# Main_Board.net
KiCad netlist of a schematic drawn in EAGLE
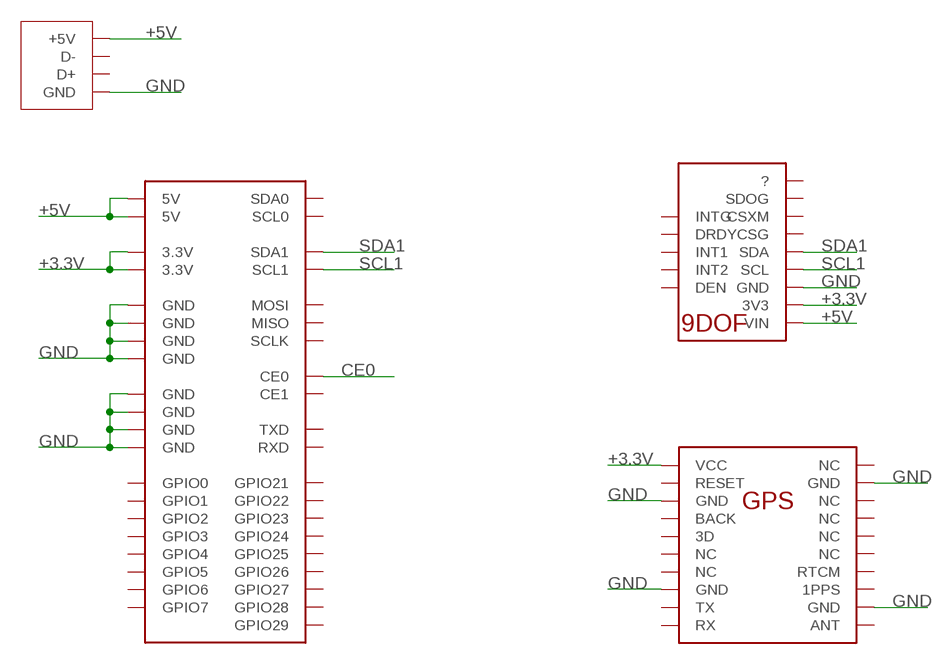
[diagram p0: schematic, sheet 1]

(export (version "E")
  (design (tool "Eeschema 10.0.6"))
  (components
    (comp (ref "U$5")
      (value "GPS")
      (footprint "eagle-import:GPS")
      (libsource (lib "eagle-import") (part "GPS"))
    )
    (comp (ref "U$6")
      (value "9DOF")
      (footprint "eagle-import:9DOF")
      (libsource (lib "eagle-import") (part "9DOF"))
    )
    (comp (ref "U$8")
      (value "USB_VERTICLE")
      (footprint "eagle-import:USB_VERTICLE")
      (libsource (lib "eagle-import") (part "USB_VERTICLE"))
    )
    (comp (ref "U$11")
      (value "PI")
      (footprint "eagle-import:PI_HEADER_SMD")
      (libsource (lib "eagle-import") (part "PI"))
    )
  )
  (nets
    (net (code "1") (name "+3.3V") (class "Default")
      (node (ref "U$11") (pin "3.3V@1") (pinfunction "3.3V_3.3V@1") (pintype "bidirectional"))
      (node (ref "U$11") (pin "3.3V@17") (pinfunction "3.3V_3.3V@17") (pintype "bidirectional"))
      (node (ref "U$5") (pin "P$1") (pinfunction "VCC_P$1") (pintype "bidirectional"))
      (node (ref "U$6") (pin "P$21") (pinfunction "3V3_P$21") (pintype "bidirectional"))
    )
    (net (code "2") (name "+5V") (class "Default")
      (node (ref "U$11") (pin "5V@2") (pinfunction "5V_5V@2") (pintype "bidirectional"))
      (node (ref "U$11") (pin "5V@4") (pinfunction "5V_5V@4") (pintype "bidirectional"))
      (node (ref "U$6") (pin "P$20") (pinfunction "VIN_P$20") (pintype "bidirectional"))
      (node (ref "U$8") (pin "VCC") (pinfunction "+5V_VCC") (pintype "bidirectional"))
    )
    (net (code "3") (name "CE0") (class "Default")
      (node (ref "U$11") (pin "CE0") (pinfunction "CE0_CE0") (pintype "bidirectional"))
    )
    (net (code "4") (name "GND") (class "Default")
      (node (ref "U$11") (pin "GND@14") (pinfunction "GND_GND@14") (pintype "bidirectional"))
      (node (ref "U$11") (pin "GND@20") (pinfunction "GND_GND@20") (pintype "bidirectional"))
      (node (ref "U$11") (pin "GND@25") (pinfunction "GND_GND@25") (pintype "bidirectional"))
      (node (ref "U$11") (pin "GND@30") (pinfunction "GND_GND@30") (pintype "bidirectional"))
      (node (ref "U$11") (pin "GND@34") (pinfunction "GND_GND@34") (pintype "bidirectional"))
      (node (ref "U$11") (pin "GND@39") (pinfunction "GND_GND@39") (pintype "bidirectional"))
      (node (ref "U$11") (pin "GND@6") (pinfunction "GND_GND@6") (pintype "bidirectional"))
      (node (ref "U$11") (pin "GND@9") (pinfunction "GND_GND@9") (pintype "bidirectional"))
      (node (ref "U$5") (pin "P$12") (pinfunction "GND_P$12") (pintype "bidirectional"))
      (node (ref "U$5") (pin "P$19") (pinfunction "GND_P$19") (pintype "bidirectional"))
      (node (ref "U$5") (pin "P$3") (pinfunction "GND_P$3") (pintype "bidirectional"))
      (node (ref "U$5") (pin "P$8") (pinfunction "GND_P$8") (pintype "bidirectional"))
      (node (ref "U$6") (pin "P$22") (pinfunction "GND_P$22") (pintype "bidirectional"))
      (node (ref "U$8") (pin "GND@1") (pinfunction "GND_GND@1") (pintype "bidirectional"))
      (node (ref "U$8") (pin "GND@2") (pinfunction "GND_GND@2") (pintype "bidirectional"))
      (node (ref "U$8") (pin "GND@3") (pinfunction "GND_GND@3") (pintype "bidirectional"))
    )
    (net (code "5") (name "SCL1") (class "Default")
      (node (ref "U$11") (pin "SCL1") (pinfunction "SCL1_SCL1") (pintype "bidirectional"))
      (node (ref "U$6") (pin "P$23") (pinfunction "SCL_P$23") (pintype "bidirectional"))
    )
    (net (code "6") (name "SDA1") (class "Default")
      (node (ref "U$11") (pin "SDA1") (pinfunction "SDA1_SDA1") (pintype "bidirectional"))
      (node (ref "U$6") (pin "P$24") (pinfunction "SDA_P$24") (pintype "bidirectional"))
    )
    (net (code "7") (name "unconnected-(U$5-1PPS-PadP$13)") (class "Default")
      (node (ref "U$5") (pin "P$13") (pinfunction "1PPS_P$13") (pintype "bidirectional"))
    )
    (net (code "8") (name "unconnected-(U$5-3D-PadP$5)") (class "Default")
      (node (ref "U$5") (pin "P$5") (pinfunction "3D_P$5") (pintype "bidirectional"))
    )
    (net (code "9") (name "unconnected-(U$5-ANT-PadP$11)") (class "Default")
      (node (ref "U$5") (pin "P$11") (pinfunction "ANT_P$11") (pintype "bidirectional"))
    )
    (net (code "10") (name "unconnected-(U$5-BACK-PadP$4)") (class "Default")
      (node (ref "U$5") (pin "P$4") (pinfunction "BACK_P$4") (pintype "bidirectional"))
    )
    (net (code "11") (name "unconnected-(U$5-NC-PadP$6)") (class "Default")
      (node (ref "U$5") (pin "P$6") (pinfunction "NC_P$6") (pintype "bidirectional"))
    )
    (net (code "12") (name "unconnected-(U$5-NC-PadP$7)") (class "Default")
      (node (ref "U$5") (pin "P$7") (pinfunction "NC_P$7") (pintype "bidirectional"))
    )
    (net (code "13") (name "unconnected-(U$5-NC-PadP$15)") (class "Default")
      (node (ref "U$5") (pin "P$15") (pinfunction "NC_P$15") (pintype "bidirectional"))
    )
    (net (code "14") (name "unconnected-(U$5-NC-PadP$16)") (class "Default")
      (node (ref "U$5") (pin "P$16") (pinfunction "NC_P$16") (pintype "bidirectional"))
    )
    (net (code "15") (name "unconnected-(U$5-NC-PadP$17)") (class "Default")
      (node (ref "U$5") (pin "P$17") (pinfunction "NC_P$17") (pintype "bidirectional"))
    )
    (net (code "16") (name "unconnected-(U$5-NC-PadP$18)") (class "Default")
      (node (ref "U$5") (pin "P$18") (pinfunction "NC_P$18") (pintype "bidirectional"))
    )
    (net (code "17") (name "unconnected-(U$5-NC-PadP$20)") (class "Default")
      (node (ref "U$5") (pin "P$20") (pinfunction "NC_P$20") (pintype "bidirectional"))
    )
    (net (code "18") (name "unconnected-(U$5-RESET-PadP$2)") (class "Default")
      (node (ref "U$5") (pin "P$2") (pinfunction "RESET_P$2") (pintype "bidirectional"))
    )
    (net (code "19") (name "unconnected-(U$5-RTCM-PadP$14)") (class "Default")
      (node (ref "U$5") (pin "P$14") (pinfunction "RTCM_P$14") (pintype "bidirectional"))
    )
    (net (code "20") (name "unconnected-(U$5-RX-PadP$10)") (class "Default")
      (node (ref "U$5") (pin "P$10") (pinfunction "RX_P$10") (pintype "bidirectional"))
    )
    (net (code "21") (name "unconnected-(U$5-TX-PadP$9)") (class "Default")
      (node (ref "U$5") (pin "P$9") (pinfunction "TX_P$9") (pintype "bidirectional"))
    )
    (net (code "22") (name "unconnected-(U$6-?-PadP$28)") (class "Default")
      (node (ref "U$6") (pin "P$28") (pinfunction "?_P$28") (pintype "bidirectional"))
    )
    (net (code "23") (name "unconnected-(U$6-CSG-PadP$25)") (class "Default")
      (node (ref "U$6") (pin "P$25") (pinfunction "CSG_P$25") (pintype "bidirectional"))
    )
    (net (code "24") (name "unconnected-(U$6-CSXM-PadP$26)") (class "Default")
      (node (ref "U$6") (pin "P$26") (pinfunction "CSXM_P$26") (pintype "bidirectional"))
    )
    (net (code "25") (name "unconnected-(U$6-DEN-PadP$15)") (class "Default")
      (node (ref "U$6") (pin "P$15") (pinfunction "DEN_P$15") (pintype "bidirectional"))
    )
    (net (code "26") (name "unconnected-(U$6-DRDY-PadP$18)") (class "Default")
      (node (ref "U$6") (pin "P$18") (pinfunction "DRDY_P$18") (pintype "bidirectional"))
    )
    (net (code "27") (name "unconnected-(U$6-INT1-PadP$17)") (class "Default")
      (node (ref "U$6") (pin "P$17") (pinfunction "INT1_P$17") (pintype "bidirectional"))
    )
    (net (code "28") (name "unconnected-(U$6-INT2-PadP$16)") (class "Default")
      (node (ref "U$6") (pin "P$16") (pinfunction "INT2_P$16") (pintype "bidirectional"))
    )
    (net (code "29") (name "unconnected-(U$6-INTG-PadP$19)") (class "Default")
      (node (ref "U$6") (pin "P$19") (pinfunction "INTG_P$19") (pintype "bidirectional"))
    )
    (net (code "30") (name "unconnected-(U$6-SDOG-PadP$27)") (class "Default")
      (node (ref "U$6") (pin "P$27") (pinfunction "SDOG_P$27") (pintype "bidirectional"))
    )
    (net (code "31") (name "unconnected-(U$8-PadD+)") (class "Default")
      (node (ref "U$8") (pin "D+") (pinfunction "D+_D+") (pintype "bidirectional"))
    )
    (net (code "32") (name "unconnected-(U$8-PadD-)") (class "Default")
      (node (ref "U$8") (pin "D-") (pinfunction "D-_D-") (pintype "bidirectional"))
    )
    (net (code "33") (name "unconnected-(U$11-PadCE1)") (class "Default")
      (node (ref "U$11") (pin "CE1") (pinfunction "CE1_CE1") (pintype "bidirectional"))
    )
    (net (code "34") (name "unconnected-(U$11-PadGPIO0)") (class "Default")
      (node (ref "U$11") (pin "GPIO0") (pinfunction "GPIO0_GPIO0") (pintype "bidirectional"))
    )
    (net (code "35") (name "unconnected-(U$11-PadGPIO1)") (class "Default")
      (node (ref "U$11") (pin "GPIO1") (pinfunction "GPIO1_GPIO1") (pintype "bidirectional"))
    )
    (net (code "36") (name "unconnected-(U$11-PadGPIO2)") (class "Default")
      (node (ref "U$11") (pin "GPIO2") (pinfunction "GPIO2_GPIO2") (pintype "bidirectional"))
    )
    (net (code "37") (name "unconnected-(U$11-PadGPIO3)") (class "Default")
      (node (ref "U$11") (pin "GPIO3") (pinfunction "GPIO3_GPIO3") (pintype "bidirectional"))
    )
    (net (code "38") (name "unconnected-(U$11-PadGPIO4)") (class "Default")
      (node (ref "U$11") (pin "GPIO4") (pinfunction "GPIO4_GPIO4") (pintype "bidirectional"))
    )
    (net (code "39") (name "unconnected-(U$11-PadGPIO5)") (class "Default")
      (node (ref "U$11") (pin "GPIO5") (pinfunction "GPIO5_GPIO5") (pintype "bidirectional"))
    )
    (net (code "40") (name "unconnected-(U$11-PadGPIO6)") (class "Default")
      (node (ref "U$11") (pin "GPIO6") (pinfunction "GPIO6_GPIO6") (pintype "bidirectional"))
    )
    (net (code "41") (name "unconnected-(U$11-PadGPIO7)") (class "Default")
      (node (ref "U$11") (pin "GPIO7") (pinfunction "GPIO7_GPIO7") (pintype "bidirectional"))
    )
    (net (code "42") (name "unconnected-(U$11-PadGPIO21)") (class "Default")
      (node (ref "U$11") (pin "GPIO21") (pinfunction "GPIO21_GPIO21") (pintype "bidirectional"))
    )
    (net (code "43") (name "unconnected-(U$11-PadGPIO22)") (class "Default")
      (node (ref "U$11") (pin "GPIO22") (pinfunction "GPIO22_GPIO22") (pintype "bidirectional"))
    )
    (net (code "44") (name "unconnected-(U$11-PadGPIO23)") (class "Default")
      (node (ref "U$11") (pin "GPIO23") (pinfunction "GPIO23_GPIO23") (pintype "bidirectional"))
    )
    (net (code "45") (name "unconnected-(U$11-PadGPIO24)") (class "Default")
      (node (ref "U$11") (pin "GPIO24") (pinfunction "GPIO24_GPIO24") (pintype "bidirectional"))
    )
    (net (code "46") (name "unconnected-(U$11-PadGPIO25)") (class "Default")
      (node (ref "U$11") (pin "GPIO25") (pinfunction "GPIO25_GPIO25") (pintype "bidirectional"))
    )
    (net (code "47") (name "unconnected-(U$11-PadGPIO26)") (class "Default")
      (node (ref "U$11") (pin "GPIO26") (pinfunction "GPIO26_GPIO26") (pintype "bidirectional"))
    )
    (net (code "48") (name "unconnected-(U$11-PadGPIO27)") (class "Default")
      (node (ref "U$11") (pin "GPIO27") (pinfunction "GPIO27_GPIO27") (pintype "bidirectional"))
    )
    (net (code "49") (name "unconnected-(U$11-PadGPIO28)") (class "Default")
      (node (ref "U$11") (pin "GPIO28") (pinfunction "GPIO28_GPIO28") (pintype "bidirectional"))
    )
    (net (code "50") (name "unconnected-(U$11-PadGPIO29)") (class "Default")
      (node (ref "U$11") (pin "GPIO29") (pinfunction "GPIO29_GPIO29") (pintype "bidirectional"))
    )
    (net (code "51") (name "unconnected-(U$11-PadMISO)") (class "Default")
      (node (ref "U$11") (pin "MISO") (pinfunction "MISO_MISO") (pintype "bidirectional"))
    )
    (net (code "52") (name "unconnected-(U$11-PadMOSI)") (class "Default")
      (node (ref "U$11") (pin "MOSI") (pinfunction "MOSI_MOSI") (pintype "bidirectional"))
    )
    (net (code "53") (name "unconnected-(U$11-PadRXD)") (class "Default")
      (node (ref "U$11") (pin "RXD") (pinfunction "RXD_RXD") (pintype "bidirectional"))
    )
    (net (code "54") (name "unconnected-(U$11-PadSCL0)") (class "Default")
      (node (ref "U$11") (pin "SCL0") (pinfunction "SCL0_SCL0") (pintype "bidirectional"))
    )
    (net (code "55") (name "unconnected-(U$11-PadSCLK)") (class "Default")
      (node (ref "U$11") (pin "SCLK") (pinfunction "SCLK_SCLK") (pintype "bidirectional"))
    )
    (net (code "56") (name "unconnected-(U$11-PadSDA0)") (class "Default")
      (node (ref "U$11") (pin "SDA0") (pinfunction "SDA0_SDA0") (pintype "bidirectional"))
    )
    (net (code "57") (name "unconnected-(U$11-PadTXD)") (class "Default")
      (node (ref "U$11") (pin "TXD") (pinfunction "TXD_TXD") (pintype "bidirectional"))
    )
  )
)
